# 1.net
KiCad netlist of a schematic drawn in Altium Designer
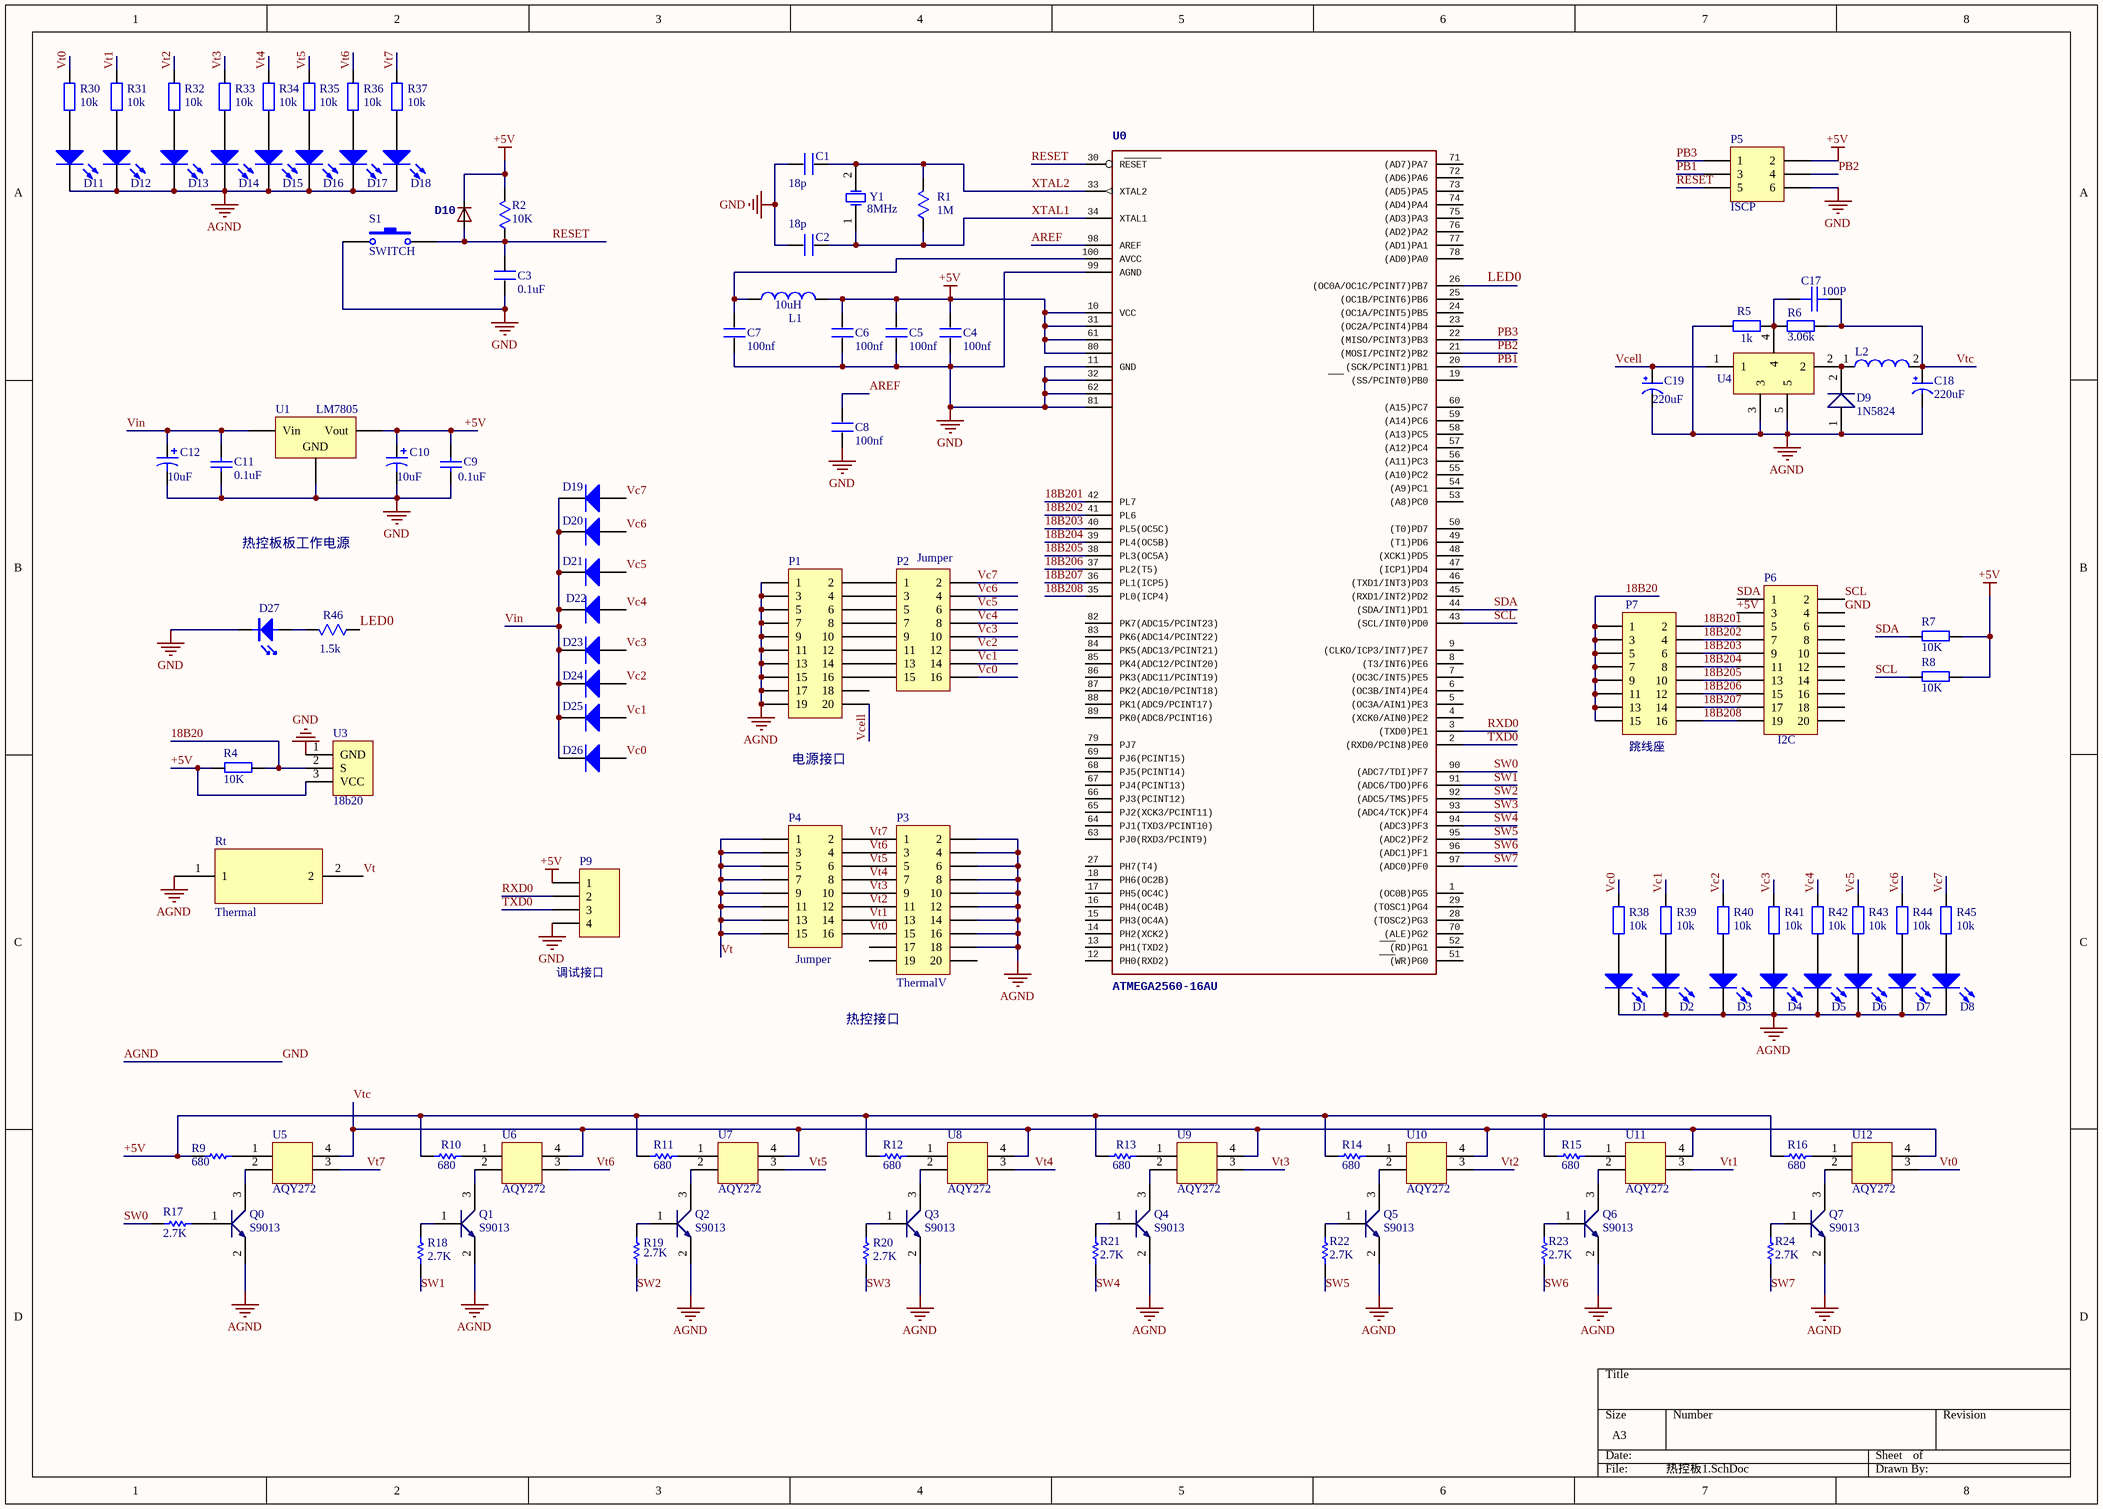
[diagram p0: 热控板1.SchDoc]

(export (version "E")
  (design (tool "Eeschema 10.0.6"))
  (components
    (comp (ref "C1") (value "18p") (footprint "CAPC3216M") (libsource (lib "STM32封装库") (part "C_1")))
    (comp (ref "C2") (value "18p") (footprint "CAPC3216M") (libsource (lib "STM32封装库") (part "C_1")))
    (comp (ref "C3") (value "0.1uF") (footprint "RESC3216M") (libsource (lib "STM32封装库") (part "C_3")))
    (comp (ref "C4") (value "100nf") (footprint "CAPC3216M") (libsource (lib "STM32封装库") (part "C")))
    (comp (ref "C5") (value "100nf") (footprint "CAPC3216M") (libsource (lib "STM32封装库") (part "C")))
    (comp (ref "C6") (value "100nf") (footprint "CAPC3216M") (libsource (lib "STM32封装库") (part "C")))
    (comp (ref "C7") (value "100nf") (footprint "CAPC3216M") (libsource (lib "STM32封装库") (part "C")))
    (comp (ref "C8") (value "100nf") (footprint "CAPC3216M") (libsource (lib "STM32封装库") (part "C")))
    (comp (ref "C9")
      (value "0.1uF")
      (footprint "CAPC3216M")
      (description "0.1uf")
      (fields (field (name "PUBLISHER") "Altium Limited"))
      (libsource (lib "Miscellaneous Devices") (part "Cap Semi"))
    )
    (comp (ref "C10")
      (value "10uF")
      (footprint "25V47uF")
      (description "10uf")
      (fields (field (name "PUBLISHER") "Altium Limited"))
      (libsource (lib "Miscellaneous Devices") (part "Cap Pol3"))
    )
    (comp (ref "C11")
      (value "0.1uF")
      (footprint "CAPC3216M")
      (description "0.1uf")
      (fields (field (name "PUBLISHER") "Altium Limited"))
      (libsource (lib "Miscellaneous Devices") (part "Cap"))
    )
    (comp (ref "C12")
      (value "10uF")
      (footprint "25V47uF")
      (description "10uf")
      (fields (field (name "PUBLISHER") "Altium Limited"))
      (libsource (lib "Miscellaneous Devices") (part "Cap Pol3"))
    )
    (comp (ref "C17")
      (value "100P")
      (footprint "CAPC3216M")
      (description "100p")
      (libsource (lib "YT1_SCH_99SE") (part "CAP"))
    )
    (comp (ref "C18") (value "220uF") (footprint "25V47uF") (libsource (lib "STM32封装库") (part "CAP")))
    (comp (ref "C19") (value "220uF") (footprint "25V47uF") (libsource (lib "STM32封装库") (part "CAP")))
    (comp (ref "D1")
      (value "LED")
      (footprint "LED")
      (description "Typical RED, GREEN, YELLOW, AMBER GaAs LED")
      (fields (field (name "PUBLISHER") "Altium Limited"))
      (libsource (lib "Miscellaneous Devices") (part "LED2"))
    )
    (comp (ref "D2")
      (value "LED")
      (footprint "LED")
      (description "Typical RED, GREEN, YELLOW, AMBER GaAs LED")
      (fields (field (name "PUBLISHER") "Altium Limited"))
      (libsource (lib "Miscellaneous Devices") (part "LED2"))
    )
    (comp (ref "D3")
      (value "LED")
      (footprint "LED")
      (description "Typical RED, GREEN, YELLOW, AMBER GaAs LED")
      (fields (field (name "PUBLISHER") "Altium Limited"))
      (libsource (lib "Miscellaneous Devices") (part "LED2"))
    )
    (comp (ref "D4")
      (value "LED")
      (footprint "LED")
      (description "Typical RED, GREEN, YELLOW, AMBER GaAs LED")
      (fields (field (name "PUBLISHER") "Altium Limited"))
      (libsource (lib "Miscellaneous Devices") (part "LED2"))
    )
    (comp (ref "D5")
      (value "LED")
      (footprint "LED")
      (description "Typical RED, GREEN, YELLOW, AMBER GaAs LED")
      (fields (field (name "PUBLISHER") "Altium Limited"))
      (libsource (lib "Miscellaneous Devices") (part "LED2"))
    )
    (comp (ref "D6")
      (value "LED")
      (footprint "LED")
      (description "Typical RED, GREEN, YELLOW, AMBER GaAs LED")
      (fields (field (name "PUBLISHER") "Altium Limited"))
      (libsource (lib "Miscellaneous Devices") (part "LED2"))
    )
    (comp (ref "D7")
      (value "LED")
      (footprint "LED")
      (description "Typical RED, GREEN, YELLOW, AMBER GaAs LED")
      (fields (field (name "PUBLISHER") "Altium Limited"))
      (libsource (lib "Miscellaneous Devices") (part "LED2"))
    )
    (comp (ref "D8")
      (value "LED")
      (footprint "LED")
      (description "Typical RED, GREEN, YELLOW, AMBER GaAs LED")
      (fields (field (name "PUBLISHER") "Altium Limited"))
      (libsource (lib "Miscellaneous Devices") (part "LED2"))
    )
    (comp (ref "D9") (value "1N5824") (footprint "DO214AC") (libsource (lib "STM32封装库") (part "1N5824")))
    (comp (ref "D10")
      (value "CD1206-S01575")
      (footprint "MINIMELF")
      (description "<b>DIODE</b>")
      (libsource (lib "Arduino_MEGA_2560-Rev3") (part "DIODE-MINIMELF"))
    )
    (comp (ref "D11")
      (value "LED")
      (footprint "LED")
      (description "Typical RED, GREEN, YELLOW, AMBER GaAs LED")
      (fields (field (name "PUBLISHER") "Altium Limited"))
      (libsource (lib "Miscellaneous Devices") (part "LED2"))
    )
    (comp (ref "D12")
      (value "LED")
      (footprint "LED")
      (description "Typical RED, GREEN, YELLOW, AMBER GaAs LED")
      (fields (field (name "PUBLISHER") "Altium Limited"))
      (libsource (lib "Miscellaneous Devices") (part "LED2"))
    )
    (comp (ref "D13")
      (value "LED")
      (footprint "LED")
      (description "Typical RED, GREEN, YELLOW, AMBER GaAs LED")
      (fields (field (name "PUBLISHER") "Altium Limited"))
      (libsource (lib "Miscellaneous Devices") (part "LED2"))
    )
    (comp (ref "D14")
      (value "LED")
      (footprint "LED")
      (description "Typical RED, GREEN, YELLOW, AMBER GaAs LED")
      (fields (field (name "PUBLISHER") "Altium Limited"))
      (libsource (lib "Miscellaneous Devices") (part "LED2"))
    )
    (comp (ref "D15")
      (value "LED")
      (footprint "LED")
      (description "Typical RED, GREEN, YELLOW, AMBER GaAs LED")
      (fields (field (name "PUBLISHER") "Altium Limited"))
      (libsource (lib "Miscellaneous Devices") (part "LED2"))
    )
    (comp (ref "D16")
      (value "LED")
      (footprint "LED")
      (description "Typical RED, GREEN, YELLOW, AMBER GaAs LED")
      (fields (field (name "PUBLISHER") "Altium Limited"))
      (libsource (lib "Miscellaneous Devices") (part "LED2"))
    )
    (comp (ref "D17")
      (value "LED")
      (footprint "LED")
      (description "Typical RED, GREEN, YELLOW, AMBER GaAs LED")
      (fields (field (name "PUBLISHER") "Altium Limited"))
      (libsource (lib "Miscellaneous Devices") (part "LED2"))
    )
    (comp (ref "D18")
      (value "LED")
      (footprint "LED")
      (description "Typical RED, GREEN, YELLOW, AMBER GaAs LED")
      (fields (field (name "PUBLISHER") "Altium Limited"))
      (libsource (lib "Miscellaneous Devices") (part "LED2"))
    )
    (comp (ref "D19")
      (value "1N4001")
      (footprint "SMB")
      (description "1 Amp General Purpose Rectifier")
      (fields (field (name "PUBLISHER") "Altium Limited"))
      (libsource (lib "Miscellaneous Devices") (part "Diode 1N4001"))
    )
    (comp (ref "D20")
      (value "1N4001")
      (footprint "SMB")
      (description "1 Amp General Purpose Rectifier")
      (fields (field (name "PUBLISHER") "Altium Limited"))
      (libsource (lib "Miscellaneous Devices") (part "Diode 1N4001"))
    )
    (comp (ref "D21")
      (value "1N4001")
      (footprint "SMB")
      (description "1 Amp General Purpose Rectifier")
      (fields (field (name "PUBLISHER") "Altium Limited"))
      (libsource (lib "Miscellaneous Devices") (part "Diode 1N4001"))
    )
    (comp (ref "D22")
      (value "1N4001")
      (footprint "SMB")
      (description "1 Amp General Purpose Rectifier")
      (fields (field (name "PUBLISHER") "Altium Limited"))
      (libsource (lib "Miscellaneous Devices") (part "Diode 1N4001"))
    )
    (comp (ref "D23")
      (value "1N4001")
      (footprint "SMB")
      (description "1 Amp General Purpose Rectifier")
      (fields (field (name "PUBLISHER") "Altium Limited"))
      (libsource (lib "Miscellaneous Devices") (part "Diode 1N4001"))
    )
    (comp (ref "D24")
      (value "1N4001")
      (footprint "SMB")
      (description "1 Amp General Purpose Rectifier")
      (fields (field (name "PUBLISHER") "Altium Limited"))
      (libsource (lib "Miscellaneous Devices") (part "Diode 1N4001"))
    )
    (comp (ref "D25")
      (value "1N4001")
      (footprint "SMB")
      (description "1 Amp General Purpose Rectifier")
      (fields (field (name "PUBLISHER") "Altium Limited"))
      (libsource (lib "Miscellaneous Devices") (part "Diode 1N4001"))
    )
    (comp (ref "D26")
      (value "1N4001")
      (footprint "SMB")
      (description "1 Amp General Purpose Rectifier")
      (fields (field (name "PUBLISHER") "Altium Limited"))
      (libsource (lib "Miscellaneous Devices") (part "Diode 1N4001"))
    )
    (comp (ref "D27") (value "DS0") (footprint "常用元件封装:LED") (libsource (lib "YT1_SCH_99SE") (part "LED")))
    (comp (ref "L1")
      (value "10uH")
      (footprint "INDC3216M")
      (description "Inductor")
      (fields (field (name "PUBLISHER") "Altium Limited"))
      (libsource (lib "Miscellaneous Devices") (part "Inductor"))
    )
    (comp (ref "L2")
      (value "inductance")
      (footprint "INDUCTANCE_1")
      (libsource (lib "STM32封装库") (part "inductance"))
    )
    (comp (ref "P1")
      (value "Power Interface")
      (footprint "HDR2X10")
      (description "Header, 10-Pin, Dual row")
      (fields (field (name "PUBLISHER") "Altium Limited"))
      (libsource (lib "Miscellaneous Connectors") (part "Header 10X2"))
    )
    (comp (ref "P2")
      (value "Jumper")
      (footprint "HDR2X8")
      (description "Header, 8-Pin, Dual row")
      (fields (field (name "PUBLISHER") "Altium Limited"))
      (libsource (lib "Miscellaneous Connectors") (part "Header 8X2"))
    )
    (comp (ref "P3")
      (value "ThermalV")
      (footprint "HDR2X10")
      (description "Header, 10-Pin, Dual row")
      (fields (field (name "PUBLISHER") "Altium Limited"))
      (libsource (lib "Miscellaneous Connectors") (part "Header 10X2"))
    )
    (comp (ref "P4")
      (value "Jumper")
      (footprint "tiepianpeizhen")
      (description "Header, 8-Pin, Dual row")
      (fields (field (name "PUBLISHER") "Altium Limited"))
      (libsource (lib "Miscellaneous Connectors") (part "Header 8X2"))
    )
    (comp (ref "P5")
      (value "ISCP")
      (footprint "HDR2X3")
      (description "Header, 3-Pin, Dual row")
      (fields (field (name "PUBLISHER") "Altium Limited"))
      (libsource (lib "Miscellaneous Connectors") (part "Header 3X2"))
    )
    (comp (ref "P6")
      (value "I2C")
      (footprint "HDR2X10")
      (description "Header, 10-Pin, Dual row")
      (fields (field (name "PUBLISHER") "Altium Limited"))
      (libsource (lib "Miscellaneous Connectors") (part "Header 10X2"))
    )
    (comp (ref "P7")
      (value "跳线座")
      (footprint "HDR2X8")
      (description "Header, 8-Pin, Dual row")
      (fields (field (name "PUBLISHER") "Altium Limited"))
      (libsource (lib "Miscellaneous Connectors") (part "Header 8X2"))
    )
    (comp (ref "P9")
      (value "调试接口")
      (footprint "HDR1X4")
      (description "Header, 4-Pin")
      (fields (field (name "PUBLISHER") "Altium Limited"))
      (libsource (lib "Miscellaneous Connectors") (part "Header 4"))
    )
    (comp (ref "Q0") (value "S9013") (footprint "SOT23") (libsource (lib "常用元件库") (part "S9013")))
    (comp (ref "Q1") (value "S9013") (footprint "SOT23") (libsource (lib "常用元件库") (part "S9013")))
    (comp (ref "Q2") (value "S9013") (footprint "SOT23") (libsource (lib "常用元件库") (part "S9013")))
    (comp (ref "Q3") (value "S9013") (footprint "SOT23") (libsource (lib "常用元件库") (part "S9013")))
    (comp (ref "Q4") (value "S9013") (footprint "SOT23") (libsource (lib "常用元件库") (part "S9013")))
    (comp (ref "Q5") (value "S9013") (footprint "SOT23") (libsource (lib "常用元件库") (part "S9013")))
    (comp (ref "Q6") (value "S9013") (footprint "SOT23") (libsource (lib "常用元件库") (part "S9013")))
    (comp (ref "Q7") (value "S9013") (footprint "SOT23") (libsource (lib "常用元件库") (part "S9013")))
    (comp (ref "R1") (value "1M") (footprint "RESC3216M") (libsource (lib "YT1_SCH_99SE") (part "RES")))
    (comp (ref "R2") (value "10K") (footprint "RESC3216M") (libsource (lib "YT1_SCH_99SE") (part "RES")))
    (comp (ref "R4") (value "10K") (footprint "RESC3216M") (libsource (lib "STM32封装库") (part "R")))
    (comp (ref "R5")
      (value "1k")
      (footprint "RESC3216M")
      (description "Resistor")
      (fields (field (name "PUBLISHER") "Altium Limited"))
      (libsource (lib "") (part "Res2_1"))
    )
    (comp (ref "R6")
      (value "3.06k")
      (footprint "RESC3216M")
      (description "Resistor")
      (fields (field (name "Comment") "5.1k") (field (name "PUBLISHER") "Altium Limited"))
      (libsource (lib "") (part "Res2_1"))
    )
    (comp (ref "R7") (value "10K") (footprint "RESC3216M") (libsource (lib "STM32封装库") (part "R")))
    (comp (ref "R8") (value "10K") (footprint "RESC3216M") (libsource (lib "STM32封装库") (part "R")))
    (comp (ref "R9")
      (value "680")
      (footprint "RESC3216M")
      (description "resistance")
      (libsource (lib "Sat_Integrated_Library") (part "Res"))
    )
    (comp (ref "R10")
      (value "680")
      (footprint "RESC3216M")
      (description "resistance")
      (libsource (lib "Sat_Integrated_Library") (part "Res"))
    )
    (comp (ref "R11")
      (value "680")
      (footprint "RESC3216M")
      (description "resistance")
      (libsource (lib "Sat_Integrated_Library") (part "Res"))
    )
    (comp (ref "R12")
      (value "680")
      (footprint "RESC3216M")
      (description "resistance")
      (libsource (lib "Sat_Integrated_Library") (part "Res"))
    )
    (comp (ref "R13")
      (value "680")
      (footprint "RESC3216M")
      (description "resistance")
      (libsource (lib "Sat_Integrated_Library") (part "Res"))
    )
    (comp (ref "R14")
      (value "680")
      (footprint "RESC3216M")
      (description "resistance")
      (libsource (lib "Sat_Integrated_Library") (part "Res"))
    )
    (comp (ref "R15")
      (value "680")
      (footprint "RESC3216M")
      (description "resistance")
      (libsource (lib "Sat_Integrated_Library") (part "Res"))
    )
    (comp (ref "R16")
      (value "680")
      (footprint "RESC3216M")
      (description "resistance")
      (libsource (lib "Sat_Integrated_Library") (part "Res"))
    )
    (comp (ref "R17")
      (value "2.7K")
      (footprint "RESC3216M")
      (description "resistance")
      (libsource (lib "Sat_Integrated_Library") (part "Res"))
    )
    (comp (ref "R18")
      (value "2.7K")
      (footprint "RESC3216M")
      (description "resistance")
      (libsource (lib "Sat_Integrated_Library") (part "Res"))
    )
    (comp (ref "R19")
      (value "2.7K")
      (footprint "RESC3216M")
      (description "resistance")
      (libsource (lib "Sat_Integrated_Library") (part "Res"))
    )
    (comp (ref "R20")
      (value "2.7K")
      (footprint "RESC3216M")
      (description "resistance")
      (libsource (lib "Sat_Integrated_Library") (part "Res"))
    )
    (comp (ref "R21")
      (value "2.7K")
      (footprint "RESC3216M")
      (description "resistance")
      (libsource (lib "Sat_Integrated_Library") (part "Res"))
    )
    (comp (ref "R22")
      (value "2.7K")
      (footprint "RESC3216M")
      (description "resistance")
      (libsource (lib "Sat_Integrated_Library") (part "Res"))
    )
    (comp (ref "R23")
      (value "2.7K")
      (footprint "RESC3216M")
      (description "resistance")
      (libsource (lib "Sat_Integrated_Library") (part "Res"))
    )
    (comp (ref "R24")
      (value "2.7K")
      (footprint "RESC3216M")
      (description "resistance")
      (libsource (lib "Sat_Integrated_Library") (part "Res"))
    )
    (comp (ref "R30")
      (value "10k")
      (footprint "RESC3216M")
      (description "5.1k")
      (fields (field (name "Comment") "10K") (field (name "PUBLISHER") "Altium Limited"))
      (libsource (lib "Miscellaneous Devices") (part "Res2"))
    )
    (comp (ref "R31")
      (value "10k")
      (footprint "RESC3216M")
      (description "5.1k")
      (fields (field (name "Comment") "10K") (field (name "PUBLISHER") "Altium Limited"))
      (libsource (lib "Miscellaneous Devices") (part "Res2"))
    )
    (comp (ref "R32")
      (value "10k")
      (footprint "RESC3216M")
      (description "5.1k")
      (fields (field (name "Comment") "10K") (field (name "PUBLISHER") "Altium Limited"))
      (libsource (lib "Miscellaneous Devices") (part "Res2"))
    )
    (comp (ref "R33")
      (value "10k")
      (footprint "RESC3216M")
      (description "5.1k")
      (fields (field (name "Comment") "10K") (field (name "PUBLISHER") "Altium Limited"))
      (libsource (lib "Miscellaneous Devices") (part "Res2"))
    )
    (comp (ref "R34")
      (value "10k")
      (footprint "RESC3216M")
      (description "5.1k")
      (fields (field (name "Comment") "10K") (field (name "PUBLISHER") "Altium Limited"))
      (libsource (lib "Miscellaneous Devices") (part "Res2"))
    )
    (comp (ref "R35")
      (value "10k")
      (footprint "RESC3216M")
      (description "5.1k")
      (fields (field (name "Comment") "10K") (field (name "PUBLISHER") "Altium Limited"))
      (libsource (lib "Miscellaneous Devices") (part "Res2"))
    )
    (comp (ref "R36")
      (value "10k")
      (footprint "RESC3216M")
      (description "5.1k")
      (fields (field (name "Comment") "10K") (field (name "PUBLISHER") "Altium Limited"))
      (libsource (lib "Miscellaneous Devices") (part "Res2"))
    )
    (comp (ref "R37")
      (value "10k")
      (footprint "RESC3216M")
      (description "5.1k")
      (fields (field (name "Comment") "10K") (field (name "PUBLISHER") "Altium Limited"))
      (libsource (lib "Miscellaneous Devices") (part "Res2"))
    )
    (comp (ref "R38")
      (value "10k")
      (footprint "RESC3216M")
      (description "5.1k")
      (fields (field (name "Comment") "10K") (field (name "PUBLISHER") "Altium Limited"))
      (libsource (lib "Miscellaneous Devices") (part "Res2"))
    )
    (comp (ref "R39")
      (value "10k")
      (footprint "RESC3216M")
      (description "5.1k")
      (fields (field (name "Comment") "10K") (field (name "PUBLISHER") "Altium Limited"))
      (libsource (lib "Miscellaneous Devices") (part "Res2"))
    )
    (comp (ref "R40")
      (value "10k")
      (footprint "RESC3216M")
      (description "5.1k")
      (fields (field (name "Comment") "10K") (field (name "PUBLISHER") "Altium Limited"))
      (libsource (lib "Miscellaneous Devices") (part "Res2"))
    )
    (comp (ref "R41")
      (value "10k")
      (footprint "RESC3216M")
      (description "5.1k")
      (fields (field (name "Comment") "10K") (field (name "PUBLISHER") "Altium Limited"))
      (libsource (lib "Miscellaneous Devices") (part "Res2"))
    )
    (comp (ref "R42")
      (value "10k")
      (footprint "RESC3216M")
      (description "5.1k")
      (fields (field (name "Comment") "10K") (field (name "PUBLISHER") "Altium Limited"))
      (libsource (lib "Miscellaneous Devices") (part "Res2"))
    )
    (comp (ref "R43")
      (value "10k")
      (footprint "RESC3216M")
      (description "5.1k")
      (fields (field (name "Comment") "10K") (field (name "PUBLISHER") "Altium Limited"))
      (libsource (lib "Miscellaneous Devices") (part "Res2"))
    )
    (comp (ref "R44")
      (value "10k")
      (footprint "RESC3216M")
      (description "5.1k")
      (fields (field (name "Comment") "10K") (field (name "PUBLISHER") "Altium Limited"))
      (libsource (lib "Miscellaneous Devices") (part "Res2"))
    )
    (comp (ref "R45")
      (value "10k")
      (footprint "RESC3216M")
      (description "5.1k")
      (fields (field (name "Comment") "10K") (field (name "PUBLISHER") "Altium Limited"))
      (libsource (lib "Miscellaneous Devices") (part "Res2"))
    )
    (comp (ref "R46") (value "1.5k") (footprint "RESC3216m") (libsource (lib "YT1_SCH_99SE") (part "RES")))
    (comp (ref "Rt") (value "Thermal") (footprint "Thermal Res") (libsource (lib "jrdz") (part "jrdz")))
    (comp (ref "S1")
      (value "SWITCH")
      (footprint "PUSH BUTTON 6x6")
      (libsource (lib "STM32封装库") (part "SWITCH"))
    )
    (comp (ref "U0")
      (value "ATMEGA2560-16AU")
      (footprint "TQFP100")
      (libsource (lib "Arduino_MEGA_2560-Rev3") (part "ATMEGA2560AU"))
    )
    (comp (ref "U1")
      (value "LM7805")
      (footprint "DPAK-3")
      (description "Voltage Regulator")
      (fields (field (name "PUBLISHER") "Altium Limited"))
      (libsource (lib "Miscellaneous Devices") (part "Volt Reg"))
    )
    (comp (ref "U3") (value "18b20") (footprint "常用元件封装:TO92") (libsource (lib "常用元件库") (part "18b20")))
    (comp (ref "U4")
      (value "LM2596SADJ")
      (footprint "TO263_5")
      (libsource (lib "STM32封装库") (part "LM2596SADJ"))
    )
    (comp (ref "U5")
      (value "AQY272")
      (footprint "AQY272")
      (libsource (lib "Sat_Integrated_Library") (part "AQY272"))
    )
    (comp (ref "U6")
      (value "AQY272")
      (footprint "AQY272")
      (libsource (lib "Sat_Integrated_Library") (part "AQY272"))
    )
    (comp (ref "U7")
      (value "AQY272")
      (footprint "AQY272")
      (libsource (lib "Sat_Integrated_Library") (part "AQY272"))
    )
    (comp (ref "U8")
      (value "AQY272")
      (footprint "AQY272")
      (libsource (lib "Sat_Integrated_Library") (part "AQY272"))
    )
    (comp (ref "U9")
      (value "AQY272")
      (footprint "AQY272")
      (libsource (lib "Sat_Integrated_Library") (part "AQY272"))
    )
    (comp (ref "U10")
      (value "AQY272")
      (footprint "AQY272")
      (libsource (lib "Sat_Integrated_Library") (part "AQY272"))
    )
    (comp (ref "U11")
      (value "AQY272")
      (footprint "AQY272")
      (libsource (lib "Sat_Integrated_Library") (part "AQY272"))
    )
    (comp (ref "U12")
      (value "AQY272")
      (footprint "AQY272")
      (libsource (lib "Sat_Integrated_Library") (part "AQY272"))
    )
    (comp (ref "Y1")
      (value "8MHz")
      (footprint "XTAL_US")
      (description "Crystal Oscillator")
      (fields (field (name "PUBLISHER") "Altium Limited"))
      (libsource (lib "STM32封装库") (part "XTAL"))
    )
  )
  (nets
    (net (code "1") (name "+5V") (class "Default")
      (node (ref "C10") (pin "1") (pinfunction "1_1") (pintype "passive"))
      (node (ref "C4") (pin "2") (pintype "passive"))
      (node (ref "C5") (pin "2") (pintype "passive"))
      (node (ref "C6") (pin "2") (pintype "passive"))
      (node (ref "C9") (pin "2") (pinfunction "2_2") (pintype "passive"))
      (node (ref "D10") (pin "C") (pinfunction "C_C") (pintype "passive"))
      (node (ref "L1") (pin "2") (pinfunction "2_2") (pintype "passive"))
      (node (ref "P5") (pin "2") (pinfunction "2_2") (pintype "passive"))
      (node (ref "P6") (pin "3") (pinfunction "3_3") (pintype "passive"))
      (node (ref "P9") (pin "1") (pinfunction "1_1") (pintype "passive"))
      (node (ref "R10") (pin "1") (pinfunction "1_1") (pintype "passive"))
      (node (ref "R11") (pin "1") (pinfunction "1_1") (pintype "passive"))
      (node (ref "R12") (pin "1") (pinfunction "1_1") (pintype "passive"))
      (node (ref "R13") (pin "1") (pinfunction "1_1") (pintype "passive"))
      (node (ref "R14") (pin "1") (pinfunction "1_1") (pintype "passive"))
      (node (ref "R15") (pin "1") (pinfunction "1_1") (pintype "passive"))
      (node (ref "R16") (pin "1") (pinfunction "1_1") (pintype "passive"))
      (node (ref "R2") (pin "2") (pinfunction "2_2") (pintype "passive"))
      (node (ref "R4") (pin "2") (pintype "passive"))
      (node (ref "R7") (pin "1") (pintype "passive"))
      (node (ref "R8") (pin "1") (pintype "passive"))
      (node (ref "R9") (pin "1") (pinfunction "1_1") (pintype "passive"))
      (node (ref "U0") (pin "10") (pinfunction "VCC_10") (pintype "power_in"))
      (node (ref "U0") (pin "31") (pinfunction "VCC1_31") (pintype "power_in"))
      (node (ref "U0") (pin "61") (pinfunction "VCC2_61") (pintype "power_in"))
      (node (ref "U0") (pin "80") (pinfunction "VCC3_80") (pintype "power_in"))
      (node (ref "U1") (pin "3") (pinfunction "Vout_3") (pintype "passive"))
      (node (ref "U3") (pin "3") (pinfunction "VCC_3") (pintype "passive"))
    )
    (net (code "2") (name "/18B20") (class "Default")
      (node (ref "P7") (pin "1") (pinfunction "1_1") (pintype "passive"))
      (node (ref "P7") (pin "11") (pinfunction "11_11") (pintype "passive"))
      (node (ref "P7") (pin "13") (pinfunction "13_13") (pintype "passive"))
      (node (ref "P7") (pin "15") (pinfunction "15_15") (pintype "passive"))
      (node (ref "P7") (pin "3") (pinfunction "3_3") (pintype "passive"))
      (node (ref "P7") (pin "5") (pinfunction "5_5") (pintype "passive"))
      (node (ref "P7") (pin "7") (pinfunction "7_7") (pintype "passive"))
      (node (ref "P7") (pin "9") (pinfunction "9_9") (pintype "passive"))
      (node (ref "R4") (pin "1") (pintype "passive"))
      (node (ref "U3") (pin "2") (pinfunction "S_2") (pintype "passive"))
    )
    (net (code "3") (name "/18B201") (class "Default")
      (node (ref "P6") (pin "5") (pinfunction "5_5") (pintype "passive"))
      (node (ref "P7") (pin "2") (pinfunction "2_2") (pintype "passive"))
      (node (ref "U0") (pin "42") (pinfunction "PL7_42") (pintype "passive"))
    )
    (net (code "4") (name "/18B202") (class "Default")
      (node (ref "P6") (pin "7") (pinfunction "7_7") (pintype "passive"))
      (node (ref "P7") (pin "4") (pinfunction "4_4") (pintype "passive"))
      (node (ref "U0") (pin "41") (pinfunction "PL6_41") (pintype "passive"))
    )
    (net (code "5") (name "/18B203") (class "Default")
      (node (ref "P6") (pin "9") (pinfunction "9_9") (pintype "passive"))
      (node (ref "P7") (pin "6") (pinfunction "6_6") (pintype "passive"))
      (node (ref "U0") (pin "40") (pinfunction "PL5(OC5C)_40") (pintype "passive"))
    )
    (net (code "6") (name "/18B204") (class "Default")
      (node (ref "P6") (pin "11") (pinfunction "11_11") (pintype "passive"))
      (node (ref "P7") (pin "8") (pinfunction "8_8") (pintype "passive"))
      (node (ref "U0") (pin "39") (pinfunction "PL4(OC5B)_39") (pintype "passive"))
    )
    (net (code "7") (name "/18B205") (class "Default")
      (node (ref "P6") (pin "13") (pinfunction "13_13") (pintype "passive"))
      (node (ref "P7") (pin "10") (pinfunction "10_10") (pintype "passive"))
      (node (ref "U0") (pin "38") (pinfunction "PL3(OC5A)_38") (pintype "passive"))
    )
    (net (code "8") (name "/18B206") (class "Default")
      (node (ref "P6") (pin "15") (pinfunction "15_15") (pintype "passive"))
      (node (ref "P7") (pin "12") (pinfunction "12_12") (pintype "passive"))
      (node (ref "U0") (pin "37") (pinfunction "PL2(T5)_37") (pintype "passive"))
    )
    (net (code "9") (name "/18B207") (class "Default")
      (node (ref "P6") (pin "17") (pinfunction "17_17") (pintype "passive"))
      (node (ref "P7") (pin "14") (pinfunction "14_14") (pintype "passive"))
      (node (ref "U0") (pin "36") (pinfunction "PL1(ICP5)_36") (pintype "passive"))
    )
    (net (code "10") (name "/18B208") (class "Default")
      (node (ref "P6") (pin "19") (pinfunction "19_19") (pintype "passive"))
      (node (ref "P7") (pin "16") (pinfunction "16_16") (pintype "passive"))
      (node (ref "U0") (pin "35") (pinfunction "PL0(ICP4)_35") (pintype "passive"))
    )
    (net (code "11") (name "/AREF") (class "Default")
      (node (ref "C8") (pin "2") (pintype "passive"))
      (node (ref "U0") (pin "98") (pinfunction "AREF_98") (pintype "passive"))
    )
    (net (code "12") (name "/LED0") (class "Default")
      (node (ref "R46") (pin "1") (pinfunction "1_1") (pintype "passive"))
      (node (ref "U0") (pin "26") (pinfunction "(OC0A/OC1C/PCINT7)PB7_26") (pintype "passive"))
    )
    (net (code "13") (name "/PB1") (class "Default")
      (node (ref "P5") (pin "3") (pinfunction "3_3") (pintype "passive"))
      (node (ref "U0") (pin "20") (pinfunction "(SCK/PCINT1)PB1_20") (pintype "passive"))
    )
    (net (code "14") (name "/PB2") (class "Default")
      (node (ref "P5") (pin "4") (pinfunction "4_4") (pintype "passive"))
      (node (ref "U0") (pin "21") (pinfunction "(MOSI/PCINT2)PB2_21") (pintype "passive"))
    )
    (net (code "15") (name "/PB3") (class "Default")
      (node (ref "P5") (pin "1") (pinfunction "1_1") (pintype "passive"))
      (node (ref "U0") (pin "22") (pinfunction "(MISO/PCINT3)PB3_22") (pintype "passive"))
    )
    (net (code "16") (name "/RESET") (class "Default")
      (node (ref "C3") (pin "2") (pintype "passive"))
      (node (ref "D10") (pin "A") (pinfunction "A_A") (pintype "passive"))
      (node (ref "P5") (pin "5") (pinfunction "5_5") (pintype "passive"))
      (node (ref "R2") (pin "1") (pinfunction "1_1") (pintype "passive"))
      (node (ref "S1") (pin "2") (pinfunction "2_2") (pintype "passive"))
      (node (ref "U0") (pin "30") (pinfunction "RESET_30") (pintype "passive"))
    )
    (net (code "17") (name "/RXD0") (class "Default")
      (node (ref "P9") (pin "2") (pinfunction "2_2") (pintype "passive"))
      (node (ref "U0") (pin "3") (pinfunction "(TXD0)PE1_3") (pintype "passive"))
    )
    (net (code "18") (name "/SCL") (class "Default")
      (node (ref "P6") (pin "2") (pinfunction "2_2") (pintype "passive"))
      (node (ref "R8") (pin "2") (pintype "passive"))
      (node (ref "U0") (pin "43") (pinfunction "(SCL/INT0)PD0_43") (pintype "passive"))
    )
    (net (code "19") (name "/SDA") (class "Default")
      (node (ref "P6") (pin "1") (pinfunction "1_1") (pintype "passive"))
      (node (ref "R7") (pin "2") (pintype "passive"))
      (node (ref "U0") (pin "44") (pinfunction "(SDA/INT1)PD1_44") (pintype "passive"))
    )
    (net (code "20") (name "/SW0") (class "Default")
      (node (ref "R17") (pin "1") (pinfunction "1_1") (pintype "passive"))
      (node (ref "U0") (pin "90") (pinfunction "(ADC7/TDI)PF7_90") (pintype "passive"))
    )
    (net (code "21") (name "/SW1") (class "Default")
      (node (ref "R18") (pin "1") (pinfunction "1_1") (pintype "passive"))
      (node (ref "U0") (pin "91") (pinfunction "(ADC6/TDO)PF6_91") (pintype "passive"))
    )
    (net (code "22") (name "/SW2") (class "Default")
      (node (ref "R19") (pin "1") (pinfunction "1_1") (pintype "passive"))
      (node (ref "U0") (pin "92") (pinfunction "(ADC5/TMS)PF5_92") (pintype "passive"))
    )
    (net (code "23") (name "/SW3") (class "Default")
      (node (ref "R20") (pin "1") (pinfunction "1_1") (pintype "passive"))
      (node (ref "U0") (pin "93") (pinfunction "(ADC4/TCK)PF4_93") (pintype "passive"))
    )
    (net (code "24") (name "/SW4") (class "Default")
      (node (ref "R21") (pin "1") (pinfunction "1_1") (pintype "passive"))
      (node (ref "U0") (pin "94") (pinfunction "(ADC3)PF3_94") (pintype "passive"))
    )
    (net (code "25") (name "/SW5") (class "Default")
      (node (ref "R22") (pin "1") (pinfunction "1_1") (pintype "passive"))
      (node (ref "U0") (pin "95") (pinfunction "(ADC2)PF2_95") (pintype "passive"))
    )
    (net (code "26") (name "/SW6") (class "Default")
      (node (ref "R23") (pin "1") (pinfunction "1_1") (pintype "passive"))
      (node (ref "U0") (pin "96") (pinfunction "(ADC1)PF1_96") (pintype "passive"))
    )
    (net (code "27") (name "/SW7") (class "Default")
      (node (ref "R24") (pin "1") (pinfunction "1_1") (pintype "passive"))
      (node (ref "U0") (pin "97") (pinfunction "(ADC0)PF0_97") (pintype "passive"))
    )
    (net (code "28") (name "/TXD0") (class "Default")
      (node (ref "P9") (pin "3") (pinfunction "3_3") (pintype "passive"))
      (node (ref "U0") (pin "2") (pinfunction "(RXD0/PCIN8)PE0_2") (pintype "passive"))
    )
    (net (code "29") (name "/Vc0") (class "Default")
      (node (ref "D26") (pin "1") (pinfunction "A_1") (pintype "passive"))
      (node (ref "P2") (pin "16") (pinfunction "16_16") (pintype "passive"))
      (node (ref "R38") (pin "2") (pinfunction "2_2") (pintype "passive"))
    )
    (net (code "30") (name "/Vc1") (class "Default")
      (node (ref "D25") (pin "1") (pinfunction "A_1") (pintype "passive"))
      (node (ref "P2") (pin "14") (pinfunction "14_14") (pintype "passive"))
      (node (ref "R39") (pin "2") (pinfunction "2_2") (pintype "passive"))
    )
    (net (code "31") (name "/Vc2") (class "Default")
      (node (ref "D24") (pin "1") (pinfunction "A_1") (pintype "passive"))
      (node (ref "P2") (pin "12") (pinfunction "12_12") (pintype "passive"))
      (node (ref "R40") (pin "2") (pinfunction "2_2") (pintype "passive"))
    )
    (net (code "32") (name "/Vc3") (class "Default")
      (node (ref "D23") (pin "1") (pinfunction "A_1") (pintype "passive"))
      (node (ref "P2") (pin "10") (pinfunction "10_10") (pintype "passive"))
      (node (ref "R41") (pin "2") (pinfunction "2_2") (pintype "passive"))
    )
    (net (code "33") (name "/Vc4") (class "Default")
      (node (ref "D22") (pin "1") (pinfunction "A_1") (pintype "passive"))
      (node (ref "P2") (pin "8") (pinfunction "8_8") (pintype "passive"))
      (node (ref "R42") (pin "2") (pinfunction "2_2") (pintype "passive"))
    )
    (net (code "34") (name "/Vc5") (class "Default")
      (node (ref "D21") (pin "1") (pinfunction "A_1") (pintype "passive"))
      (node (ref "P2") (pin "6") (pinfunction "6_6") (pintype "passive"))
      (node (ref "R43") (pin "2") (pinfunction "2_2") (pintype "passive"))
    )
    (net (code "35") (name "/Vc6") (class "Default")
      (node (ref "D20") (pin "1") (pinfunction "A_1") (pintype "passive"))
      (node (ref "P2") (pin "4") (pinfunction "4_4") (pintype "passive"))
      (node (ref "R44") (pin "2") (pinfunction "2_2") (pintype "passive"))
    )
    (net (code "36") (name "/Vc7") (class "Default")
      (node (ref "D19") (pin "1") (pinfunction "A_1") (pintype "passive"))
      (node (ref "P2") (pin "2") (pinfunction "2_2") (pintype "passive"))
      (node (ref "R45") (pin "2") (pinfunction "2_2") (pintype "passive"))
    )
    (net (code "37") (name "/Vcell") (class "Default")
      (node (ref "C19") (pin "1") (pinfunction "VCC_1") (pintype "passive"))
      (node (ref "P1") (pin "20") (pinfunction "20_20") (pintype "passive"))
      (node (ref "U4") (pin "1") (pinfunction "1_1") (pintype "passive"))
    )
    (net (code "38") (name "/Vin") (class "Default")
      (node (ref "C11") (pin "2") (pinfunction "2_2") (pintype "passive"))
      (node (ref "C12") (pin "1") (pinfunction "1_1") (pintype "passive"))
      (node (ref "D19") (pin "2") (pinfunction "K_2") (pintype "passive"))
      (node (ref "D20") (pin "2") (pinfunction "K_2") (pintype "passive"))
      (node (ref "D21") (pin "2") (pinfunction "K_2") (pintype "passive"))
      (node (ref "D22") (pin "2") (pinfunction "K_2") (pintype "passive"))
      (node (ref "D23") (pin "2") (pinfunction "K_2") (pintype "passive"))
      (node (ref "D24") (pin "2") (pinfunction "K_2") (pintype "passive"))
      (node (ref "D25") (pin "2") (pinfunction "K_2") (pintype "passive"))
      (node (ref "D26") (pin "2") (pinfunction "K_2") (pintype "passive"))
      (node (ref "U1") (pin "1") (pinfunction "Vin_1") (pintype "passive"))
    )
    (net (code "39") (name "/Vt") (class "Default")
      (node (ref "P4") (pin "1") (pinfunction "1_1") (pintype "passive"))
      (node (ref "P4") (pin "11") (pinfunction "11_11") (pintype "passive"))
      (node (ref "P4") (pin "13") (pinfunction "13_13") (pintype "passive"))
      (node (ref "P4") (pin "15") (pinfunction "15_15") (pintype "passive"))
      (node (ref "P4") (pin "3") (pinfunction "3_3") (pintype "passive"))
      (node (ref "P4") (pin "5") (pinfunction "5_5") (pintype "passive"))
      (node (ref "P4") (pin "7") (pinfunction "7_7") (pintype "passive"))
      (node (ref "P4") (pin "9") (pinfunction "9_9") (pintype "passive"))
      (node (ref "Rt") (pin "2") (pinfunction "2_2") (pintype "passive"))
    )
    (net (code "40") (name "/Vt0") (class "Default")
      (node (ref "P3") (pin "15") (pinfunction "15_15") (pintype "passive"))
      (node (ref "P4") (pin "16") (pinfunction "16_16") (pintype "passive"))
      (node (ref "R30") (pin "2") (pinfunction "2_2") (pintype "passive"))
      (node (ref "U12") (pin "3") (pinfunction "3_3") (pintype "passive"))
    )
    (net (code "41") (name "/Vt1") (class "Default")
      (node (ref "P3") (pin "13") (pinfunction "13_13") (pintype "passive"))
      (node (ref "P4") (pin "14") (pinfunction "14_14") (pintype "passive"))
      (node (ref "R31") (pin "2") (pinfunction "2_2") (pintype "passive"))
      (node (ref "U11") (pin "3") (pinfunction "3_3") (pintype "passive"))
    )
    (net (code "42") (name "/Vt2") (class "Default")
      (node (ref "P3") (pin "11") (pinfunction "11_11") (pintype "passive"))
      (node (ref "P4") (pin "12") (pinfunction "12_12") (pintype "passive"))
      (node (ref "R32") (pin "2") (pinfunction "2_2") (pintype "passive"))
      (node (ref "U10") (pin "3") (pinfunction "3_3") (pintype "passive"))
    )
    (net (code "43") (name "/Vt3") (class "Default")
      (node (ref "P3") (pin "9") (pinfunction "9_9") (pintype "passive"))
      (node (ref "P4") (pin "10") (pinfunction "10_10") (pintype "passive"))
      (node (ref "R33") (pin "2") (pinfunction "2_2") (pintype "passive"))
      (node (ref "U9") (pin "3") (pinfunction "3_3") (pintype "passive"))
    )
    (net (code "44") (name "/Vt4") (class "Default")
      (node (ref "P3") (pin "7") (pinfunction "7_7") (pintype "passive"))
      (node (ref "P4") (pin "8") (pinfunction "8_8") (pintype "passive"))
      (node (ref "R34") (pin "2") (pinfunction "2_2") (pintype "passive"))
      (node (ref "U8") (pin "3") (pinfunction "3_3") (pintype "passive"))
    )
    (net (code "45") (name "/Vt5") (class "Default")
      (node (ref "P3") (pin "5") (pinfunction "5_5") (pintype "passive"))
      (node (ref "P4") (pin "6") (pinfunction "6_6") (pintype "passive"))
      (node (ref "R35") (pin "2") (pinfunction "2_2") (pintype "passive"))
      (node (ref "U7") (pin "3") (pinfunction "3_3") (pintype "passive"))
    )
    (net (code "46") (name "/Vt6") (class "Default")
      (node (ref "P3") (pin "3") (pinfunction "3_3") (pintype "passive"))
      (node (ref "P4") (pin "4") (pinfunction "4_4") (pintype "passive"))
      (node (ref "R36") (pin "2") (pinfunction "2_2") (pintype "passive"))
      (node (ref "U6") (pin "3") (pinfunction "3_3") (pintype "passive"))
    )
    (net (code "47") (name "/Vt7") (class "Default")
      (node (ref "P3") (pin "1") (pinfunction "1_1") (pintype "passive"))
      (node (ref "P4") (pin "2") (pinfunction "2_2") (pintype "passive"))
      (node (ref "R37") (pin "2") (pinfunction "2_2") (pintype "passive"))
      (node (ref "U5") (pin "3") (pinfunction "3_3") (pintype "passive"))
    )
    (net (code "48") (name "/Vtc") (class "Default")
      (node (ref "C17") (pin "2") (pinfunction "2_2") (pintype "passive"))
      (node (ref "C18") (pin "1") (pinfunction "VCC_1") (pintype "passive"))
      (node (ref "L2") (pin "2") (pinfunction "2_2") (pintype "passive"))
      (node (ref "R6") (pin "1") (pinfunction "1_1") (pintype "passive"))
      (node (ref "U10") (pin "4") (pinfunction "4_4") (pintype "passive"))
      (node (ref "U11") (pin "4") (pinfunction "4_4") (pintype "passive"))
      (node (ref "U12") (pin "4") (pinfunction "4_4") (pintype "passive"))
      (node (ref "U5") (pin "4") (pinfunction "4_4") (pintype "passive"))
      (node (ref "U6") (pin "4") (pinfunction "4_4") (pintype "passive"))
      (node (ref "U7") (pin "4") (pinfunction "4_4") (pintype "passive"))
      (node (ref "U8") (pin "4") (pinfunction "4_4") (pintype "passive"))
      (node (ref "U9") (pin "4") (pinfunction "4_4") (pintype "passive"))
    )
    (net (code "49") (name "/XTAL1") (class "Default")
      (node (ref "C2") (pin "2") (pintype "passive"))
      (node (ref "R1") (pin "1") (pinfunction "1_1") (pintype "passive"))
      (node (ref "U0") (pin "34") (pinfunction "XTAL1_34") (pintype "passive"))
      (node (ref "Y1") (pin "1") (pinfunction "OSC1_1") (pintype "passive"))
    )
    (net (code "50") (name "/XTAL2") (class "Default")
      (node (ref "C1") (pin "2") (pintype "passive"))
      (node (ref "R1") (pin "2") (pinfunction "2_2") (pintype "passive"))
      (node (ref "U0") (pin "33") (pinfunction "XTAL2_33") (pintype "output"))
      (node (ref "Y1") (pin "2") (pinfunction "OSC2_2") (pintype "passive"))
    )
    (net (code "51") (name "AGND") (class "Default")
      (node (ref "C1") (pin "1") (pintype "passive"))
      (node (ref "C10") (pin "2") (pinfunction "2_2") (pintype "passive"))
      (node (ref "C11") (pin "1") (pinfunction "1_1") (pintype "passive"))
      (node (ref "C12") (pin "2") (pinfunction "2_2") (pintype "passive"))
      (node (ref "C18") (pin "2") (pinfunction "GND_2") (pintype "passive"))
      (node (ref "C19") (pin "2") (pinfunction "GND_2") (pintype "passive"))
      (node (ref "C2") (pin "1") (pintype "passive"))
      (node (ref "C3") (pin "1") (pintype "passive"))
      (node (ref "C4") (pin "1") (pintype "passive"))
      (node (ref "C5") (pin "1") (pintype "passive"))
      (node (ref "C6") (pin "1") (pintype "passive"))
      (node (ref "C7") (pin "1") (pintype "passive"))
      (node (ref "C8") (pin "1") (pintype "passive"))
      (node (ref "C9") (pin "1") (pinfunction "1_1") (pintype "passive"))
      (node (ref "D1") (pin "2") (pinfunction "K_2") (pintype "passive"))
      (node (ref "D11") (pin "2") (pinfunction "K_2") (pintype "passive"))
      (node (ref "D12") (pin "2") (pinfunction "K_2") (pintype "passive"))
      (node (ref "D13") (pin "2") (pinfunction "K_2") (pintype "passive"))
      (node (ref "D14") (pin "2") (pinfunction "K_2") (pintype "passive"))
      (node (ref "D15") (pin "2") (pinfunction "K_2") (pintype "passive"))
      (node (ref "D16") (pin "2") (pinfunction "K_2") (pintype "passive"))
      (node (ref "D17") (pin "2") (pinfunction "K_2") (pintype "passive"))
      (node (ref "D18") (pin "2") (pinfunction "K_2") (pintype "passive"))
      (node (ref "D2") (pin "2") (pinfunction "K_2") (pintype "passive"))
      (node (ref "D27") (pin "2") (pinfunction "2_2") (pintype "passive"))
      (node (ref "D3") (pin "2") (pinfunction "K_2") (pintype "passive"))
      (node (ref "D4") (pin "2") (pinfunction "K_2") (pintype "passive"))
      (node (ref "D5") (pin "2") (pinfunction "K_2") (pintype "passive"))
      (node (ref "D6") (pin "2") (pinfunction "K_2") (pintype "passive"))
      (node (ref "D7") (pin "2") (pinfunction "K_2") (pintype "passive"))
      (node (ref "D8") (pin "2") (pinfunction "K_2") (pintype "passive"))
      (node (ref "D9") (pin "1") (pinfunction "1_1") (pintype "passive"))
      (node (ref "P1") (pin "1") (pinfunction "1_1") (pintype "passive"))
      (node (ref "P1") (pin "11") (pinfunction "11_11") (pintype "passive"))
      (node (ref "P1") (pin "13") (pinfunction "13_13") (pintype "passive"))
      (node (ref "P1") (pin "15") (pinfunction "15_15") (pintype "passive"))
      (node (ref "P1") (pin "17") (pinfunction "17_17") (pintype "passive"))
      (node (ref "P1") (pin "19") (pinfunction "19_19") (pintype "passive"))
      (node (ref "P1") (pin "3") (pinfunction "3_3") (pintype "passive"))
      (node (ref "P1") (pin "5") (pinfunction "5_5") (pintype "passive"))
      (node (ref "P1") (pin "7") (pinfunction "7_7") (pintype "passive"))
      (node (ref "P1") (pin "9") (pinfunction "9_9") (pintype "passive"))
      (node (ref "P3") (pin "10") (pinfunction "10_10") (pintype "passive"))
      (node (ref "P3") (pin "12") (pinfunction "12_12") (pintype "passive"))
      (node (ref "P3") (pin "14") (pinfunction "14_14") (pintype "passive"))
      (node (ref "P3") (pin "16") (pinfunction "16_16") (pintype "passive"))
      (node (ref "P3") (pin "18") (pinfunction "18_18") (pintype "passive"))
      (node (ref "P3") (pin "2") (pinfunction "2_2") (pintype "passive"))
      (node (ref "P3") (pin "4") (pinfunction "4_4") (pintype "passive"))
      (node (ref "P3") (pin "6") (pinfunction "6_6") (pintype "passive"))
      (node (ref "P3") (pin "8") (pinfunction "8_8") (pintype "passive"))
      (node (ref "P5") (pin "6") (pinfunction "6_6") (pintype "passive"))
      (node (ref "P6") (pin "4") (pinfunction "4_4") (pintype "passive"))
      (node (ref "P9") (pin "4") (pinfunction "4_4") (pintype "passive"))
      (node (ref "Q0") (pin "2") (pinfunction "2_2") (pintype "passive"))
      (node (ref "Q1") (pin "2") (pinfunction "2_2") (pintype "passive"))
      (node (ref "Q2") (pin "2") (pinfunction "2_2") (pintype "passive"))
      (node (ref "Q3") (pin "2") (pinfunction "2_2") (pintype "passive"))
      (node (ref "Q4") (pin "2") (pinfunction "2_2") (pintype "passive"))
      (node (ref "Q5") (pin "2") (pinfunction "2_2") (pintype "passive"))
      (node (ref "Q6") (pin "2") (pinfunction "2_2") (pintype "passive"))
      (node (ref "Q7") (pin "2") (pinfunction "2_2") (pintype "passive"))
      (node (ref "R5") (pin "2") (pinfunction "2_2") (pintype "passive"))
      (node (ref "Rt") (pin "1") (pinfunction "1_1") (pintype "passive"))
      (node (ref "S1") (pin "1") (pinfunction "1_1") (pintype "passive"))
      (node (ref "U0") (pin "11") (pinfunction "GND_11") (pintype "power_in"))
      (node (ref "U0") (pin "32") (pinfunction "GND1_32") (pintype "power_in"))
      (node (ref "U0") (pin "62") (pinfunction "GND2_62") (pintype "power_in"))
      (node (ref "U0") (pin "81") (pinfunction "GND3_81") (pintype "power_in"))
      (node (ref "U0") (pin "99") (pinfunction "AGND_99") (pintype "power_in"))
      (node (ref "U1") (pin "2") (pinfunction "GND_2") (pintype "passive"))
      (node (ref "U3") (pin "1") (pinfunction "GND_1") (pintype "passive"))
      (node (ref "U4") (pin "3") (pinfunction "3_3") (pintype "passive"))
      (node (ref "U4") (pin "5") (pinfunction "5_5") (pintype "passive"))
    )
    (net (code "52") (name "Net-(C17-Pad1)") (class "Default")
      (node (ref "C17") (pin "1") (pinfunction "1_1") (pintype "passive"))
      (node (ref "R5") (pin "1") (pinfunction "1_1") (pintype "passive"))
      (node (ref "R6") (pin "2") (pinfunction "2_2") (pintype "passive"))
      (node (ref "U4") (pin "4") (pinfunction "4_4") (pintype "passive"))
    )
    (net (code "53") (name "Net-(D1-A)") (class "Default")
      (node (ref "D1") (pin "1") (pinfunction "A_1") (pintype "passive"))
      (node (ref "R38") (pin "1") (pinfunction "1_1") (pintype "passive"))
    )
    (net (code "54") (name "Net-(D2-A)") (class "Default")
      (node (ref "D2") (pin "1") (pinfunction "A_1") (pintype "passive"))
      (node (ref "R39") (pin "1") (pinfunction "1_1") (pintype "passive"))
    )
    (net (code "55") (name "Net-(D3-A)") (class "Default")
      (node (ref "D3") (pin "1") (pinfunction "A_1") (pintype "passive"))
      (node (ref "R40") (pin "1") (pinfunction "1_1") (pintype "passive"))
    )
    (net (code "56") (name "Net-(D4-A)") (class "Default")
      (node (ref "D4") (pin "1") (pinfunction "A_1") (pintype "passive"))
      (node (ref "R41") (pin "1") (pinfunction "1_1") (pintype "passive"))
    )
    (net (code "57") (name "Net-(D5-A)") (class "Default")
      (node (ref "D5") (pin "1") (pinfunction "A_1") (pintype "passive"))
      (node (ref "R42") (pin "1") (pinfunction "1_1") (pintype "passive"))
    )
    (net (code "58") (name "Net-(D6-A)") (class "Default")
      (node (ref "D6") (pin "1") (pinfunction "A_1") (pintype "passive"))
      (node (ref "R43") (pin "1") (pinfunction "1_1") (pintype "passive"))
    )
    (net (code "59") (name "Net-(D7-A)") (class "Default")
      (node (ref "D7") (pin "1") (pinfunction "A_1") (pintype "passive"))
      (node (ref "R44") (pin "1") (pinfunction "1_1") (pintype "passive"))
    )
    (net (code "60") (name "Net-(D8-A)") (class "Default")
      (node (ref "D8") (pin "1") (pinfunction "A_1") (pintype "passive"))
      (node (ref "R45") (pin "1") (pinfunction "1_1") (pintype "passive"))
    )
    (net (code "61") (name "Net-(D9-Pad2)") (class "Default")
      (node (ref "D9") (pin "2") (pinfunction "2_2") (pintype "passive"))
      (node (ref "L2") (pin "1") (pinfunction "1_1") (pintype "passive"))
      (node (ref "U4") (pin "2") (pinfunction "2_2") (pintype "passive"))
    )
    (net (code "62") (name "Net-(D11-A)") (class "Default")
      (node (ref "D11") (pin "1") (pinfunction "A_1") (pintype "passive"))
      (node (ref "R30") (pin "1") (pinfunction "1_1") (pintype "passive"))
    )
    (net (code "63") (name "Net-(D12-A)") (class "Default")
      (node (ref "D12") (pin "1") (pinfunction "A_1") (pintype "passive"))
      (node (ref "R31") (pin "1") (pinfunction "1_1") (pintype "passive"))
    )
    (net (code "64") (name "Net-(D13-A)") (class "Default")
      (node (ref "D13") (pin "1") (pinfunction "A_1") (pintype "passive"))
      (node (ref "R32") (pin "1") (pinfunction "1_1") (pintype "passive"))
    )
    (net (code "65") (name "Net-(D14-A)") (class "Default")
      (node (ref "D14") (pin "1") (pinfunction "A_1") (pintype "passive"))
      (node (ref "R33") (pin "1") (pinfunction "1_1") (pintype "passive"))
    )
    (net (code "66") (name "Net-(D15-A)") (class "Default")
      (node (ref "D15") (pin "1") (pinfunction "A_1") (pintype "passive"))
      (node (ref "R34") (pin "1") (pinfunction "1_1") (pintype "passive"))
    )
    (net (code "67") (name "Net-(D16-A)") (class "Default")
      (node (ref "D16") (pin "1") (pinfunction "A_1") (pintype "passive"))
      (node (ref "R35") (pin "1") (pinfunction "1_1") (pintype "passive"))
    )
    (net (code "68") (name "Net-(D17-A)") (class "Default")
      (node (ref "D17") (pin "1") (pinfunction "A_1") (pintype "passive"))
      (node (ref "R36") (pin "1") (pinfunction "1_1") (pintype "passive"))
    )
    (net (code "69") (name "Net-(D18-A)") (class "Default")
      (node (ref "D18") (pin "1") (pinfunction "A_1") (pintype "passive"))
      (node (ref "R37") (pin "1") (pinfunction "1_1") (pintype "passive"))
    )
    (net (code "70") (name "Net-(D27-Pad1)") (class "Default")
      (node (ref "D27") (pin "1") (pinfunction "1_1") (pintype "passive"))
      (node (ref "R46") (pin "2") (pinfunction "2_2") (pintype "passive"))
    )
    (net (code "71") (name "Net-(P1-Pad2)") (class "Default")
      (node (ref "P1") (pin "2") (pinfunction "2_2") (pintype "passive"))
      (node (ref "P2") (pin "1") (pinfunction "1_1") (pintype "passive"))
    )
    (net (code "72") (name "Net-(P1-Pad4)") (class "Default")
      (node (ref "P1") (pin "4") (pinfunction "4_4") (pintype "passive"))
      (node (ref "P2") (pin "3") (pinfunction "3_3") (pintype "passive"))
    )
    (net (code "73") (name "Net-(P1-Pad6)") (class "Default")
      (node (ref "P1") (pin "6") (pinfunction "6_6") (pintype "passive"))
      (node (ref "P2") (pin "5") (pinfunction "5_5") (pintype "passive"))
    )
    (net (code "74") (name "Net-(P1-Pad8)") (class "Default")
      (node (ref "P1") (pin "8") (pinfunction "8_8") (pintype "passive"))
      (node (ref "P2") (pin "7") (pinfunction "7_7") (pintype "passive"))
    )
    (net (code "75") (name "Net-(P1-Pad10)") (class "Default")
      (node (ref "P1") (pin "10") (pinfunction "10_10") (pintype "passive"))
      (node (ref "P2") (pin "9") (pinfunction "9_9") (pintype "passive"))
    )
    (net (code "76") (name "Net-(P1-Pad12)") (class "Default")
      (node (ref "P1") (pin "12") (pinfunction "12_12") (pintype "passive"))
      (node (ref "P2") (pin "11") (pinfunction "11_11") (pintype "passive"))
    )
    (net (code "77") (name "Net-(P1-Pad14)") (class "Default")
      (node (ref "P1") (pin "14") (pinfunction "14_14") (pintype "passive"))
      (node (ref "P2") (pin "13") (pinfunction "13_13") (pintype "passive"))
    )
    (net (code "78") (name "Net-(P1-Pad16)") (class "Default")
      (node (ref "P1") (pin "16") (pinfunction "16_16") (pintype "passive"))
      (node (ref "P2") (pin "15") (pinfunction "15_15") (pintype "passive"))
    )
    (net (code "79") (name "Net-(Q0-Pad1)") (class "Default")
      (node (ref "Q0") (pin "1") (pinfunction "1_1") (pintype "passive"))
      (node (ref "R17") (pin "2") (pinfunction "2_2") (pintype "passive"))
    )
    (net (code "80") (name "Net-(Q0-Pad3)") (class "Default")
      (node (ref "Q0") (pin "3") (pinfunction "3_3") (pintype "passive"))
      (node (ref "U5") (pin "2") (pinfunction "2_2") (pintype "passive"))
    )
    (net (code "81") (name "Net-(Q1-Pad1)") (class "Default")
      (node (ref "Q1") (pin "1") (pinfunction "1_1") (pintype "passive"))
      (node (ref "R18") (pin "2") (pinfunction "2_2") (pintype "passive"))
    )
    (net (code "82") (name "Net-(Q1-Pad3)") (class "Default")
      (node (ref "Q1") (pin "3") (pinfunction "3_3") (pintype "passive"))
      (node (ref "U6") (pin "2") (pinfunction "2_2") (pintype "passive"))
    )
    (net (code "83") (name "Net-(Q2-Pad1)") (class "Default")
      (node (ref "Q2") (pin "1") (pinfunction "1_1") (pintype "passive"))
      (node (ref "R19") (pin "2") (pinfunction "2_2") (pintype "passive"))
    )
    (net (code "84") (name "Net-(Q2-Pad3)") (class "Default")
      (node (ref "Q2") (pin "3") (pinfunction "3_3") (pintype "passive"))
      (node (ref "U7") (pin "2") (pinfunction "2_2") (pintype "passive"))
    )
    (net (code "85") (name "Net-(Q3-Pad1)") (class "Default")
      (node (ref "Q3") (pin "1") (pinfunction "1_1") (pintype "passive"))
      (node (ref "R20") (pin "2") (pinfunction "2_2") (pintype "passive"))
    )
    (net (code "86") (name "Net-(Q3-Pad3)") (class "Default")
      (node (ref "Q3") (pin "3") (pinfunction "3_3") (pintype "passive"))
      (node (ref "U8") (pin "2") (pinfunction "2_2") (pintype "passive"))
    )
    (net (code "87") (name "Net-(Q4-Pad1)") (class "Default")
      (node (ref "Q4") (pin "1") (pinfunction "1_1") (pintype "passive"))
      (node (ref "R21") (pin "2") (pinfunction "2_2") (pintype "passive"))
    )
    (net (code "88") (name "Net-(Q4-Pad3)") (class "Default")
      (node (ref "Q4") (pin "3") (pinfunction "3_3") (pintype "passive"))
      (node (ref "U9") (pin "2") (pinfunction "2_2") (pintype "passive"))
    )
    (net (code "89") (name "Net-(Q5-Pad1)") (class "Default")
      (node (ref "Q5") (pin "1") (pinfunction "1_1") (pintype "passive"))
      (node (ref "R22") (pin "2") (pinfunction "2_2") (pintype "passive"))
    )
    (net (code "90") (name "Net-(Q5-Pad3)") (class "Default")
      (node (ref "Q5") (pin "3") (pinfunction "3_3") (pintype "passive"))
      (node (ref "U10") (pin "2") (pinfunction "2_2") (pintype "passive"))
    )
    (net (code "91") (name "Net-(Q6-Pad1)") (class "Default")
      (node (ref "Q6") (pin "1") (pinfunction "1_1") (pintype "passive"))
      (node (ref "R23") (pin "2") (pinfunction "2_2") (pintype "passive"))
    )
    (net (code "92") (name "Net-(Q6-Pad3)") (class "Default")
      (node (ref "Q6") (pin "3") (pinfunction "3_3") (pintype "passive"))
      (node (ref "U11") (pin "2") (pinfunction "2_2") (pintype "passive"))
    )
    (net (code "93") (name "Net-(Q7-Pad1)") (class "Default")
      (node (ref "Q7") (pin "1") (pinfunction "1_1") (pintype "passive"))
      (node (ref "R24") (pin "2") (pinfunction "2_2") (pintype "passive"))
    )
    (net (code "94") (name "Net-(Q7-Pad3)") (class "Default")
      (node (ref "Q7") (pin "3") (pinfunction "3_3") (pintype "passive"))
      (node (ref "U12") (pin "2") (pinfunction "2_2") (pintype "passive"))
    )
    (net (code "95") (name "Net-(R9-Pad2)") (class "Default")
      (node (ref "R9") (pin "2") (pinfunction "2_2") (pintype "passive"))
      (node (ref "U5") (pin "1") (pinfunction "1_1") (pintype "passive"))
    )
    (net (code "96") (name "Net-(R10-Pad2)") (class "Default")
      (node (ref "R10") (pin "2") (pinfunction "2_2") (pintype "passive"))
      (node (ref "U6") (pin "1") (pinfunction "1_1") (pintype "passive"))
    )
    (net (code "97") (name "Net-(R11-Pad2)") (class "Default")
      (node (ref "R11") (pin "2") (pinfunction "2_2") (pintype "passive"))
      (node (ref "U7") (pin "1") (pinfunction "1_1") (pintype "passive"))
    )
    (net (code "98") (name "Net-(R12-Pad2)") (class "Default")
      (node (ref "R12") (pin "2") (pinfunction "2_2") (pintype "passive"))
      (node (ref "U8") (pin "1") (pinfunction "1_1") (pintype "passive"))
    )
    (net (code "99") (name "Net-(R13-Pad2)") (class "Default")
      (node (ref "R13") (pin "2") (pinfunction "2_2") (pintype "passive"))
      (node (ref "U9") (pin "1") (pinfunction "1_1") (pintype "passive"))
    )
    (net (code "100") (name "Net-(R14-Pad2)") (class "Default")
      (node (ref "R14") (pin "2") (pinfunction "2_2") (pintype "passive"))
      (node (ref "U10") (pin "1") (pinfunction "1_1") (pintype "passive"))
    )
    (net (code "101") (name "Net-(R15-Pad2)") (class "Default")
      (node (ref "R15") (pin "2") (pinfunction "2_2") (pintype "passive"))
      (node (ref "U11") (pin "1") (pinfunction "1_1") (pintype "passive"))
    )
    (net (code "102") (name "Net-(R16-Pad2)") (class "Default")
      (node (ref "R16") (pin "2") (pinfunction "2_2") (pintype "passive"))
      (node (ref "U12") (pin "1") (pinfunction "1_1") (pintype "passive"))
    )
    (net (code "103") (name "Net-(U0-AVCC)") (class "Default")
      (node (ref "C7") (pin "2") (pintype "passive"))
      (node (ref "L1") (pin "1") (pinfunction "1_1") (pintype "passive"))
      (node (ref "U0") (pin "100") (pinfunction "AVCC_100") (pintype "power_in"))
    )
    (net (code "104") (name "unconnected-(P1-Pad18)") (class "Default")
      (node (ref "P1") (pin "18") (pinfunction "18_18") (pintype "passive"))
    )
    (net (code "105") (name "unconnected-(P3-Pad17)") (class "Default")
      (node (ref "P3") (pin "17") (pinfunction "17_17") (pintype "passive"))
    )
    (net (code "106") (name "unconnected-(P3-Pad19)") (class "Default")
      (node (ref "P3") (pin "19") (pinfunction "19_19") (pintype "passive"))
    )
    (net (code "107") (name "unconnected-(P3-Pad20)") (class "Default")
      (node (ref "P3") (pin "20") (pinfunction "20_20") (pintype "passive"))
    )
    (net (code "108") (name "unconnected-(P6-Pad6)") (class "Default")
      (node (ref "P6") (pin "6") (pinfunction "6_6") (pintype "passive"))
    )
    (net (code "109") (name "unconnected-(P6-Pad8)") (class "Default")
      (node (ref "P6") (pin "8") (pinfunction "8_8") (pintype "passive"))
    )
    (net (code "110") (name "unconnected-(P6-Pad10)") (class "Default")
      (node (ref "P6") (pin "10") (pinfunction "10_10") (pintype "passive"))
    )
    (net (code "111") (name "unconnected-(P6-Pad12)") (class "Default")
      (node (ref "P6") (pin "12") (pinfunction "12_12") (pintype "passive"))
    )
    (net (code "112") (name "unconnected-(P6-Pad14)") (class "Default")
      (node (ref "P6") (pin "14") (pinfunction "14_14") (pintype "passive"))
    )
    (net (code "113") (name "unconnected-(P6-Pad16)") (class "Default")
      (node (ref "P6") (pin "16") (pinfunction "16_16") (pintype "passive"))
    )
    (net (code "114") (name "unconnected-(P6-Pad18)") (class "Default")
      (node (ref "P6") (pin "18") (pinfunction "18_18") (pintype "passive"))
    )
    (net (code "115") (name "unconnected-(P6-Pad20)") (class "Default")
      (node (ref "P6") (pin "20") (pinfunction "20_20") (pintype "passive"))
    )
    (net (code "116") (name "unconnected-(U0-(A8)PC0-Pad53)") (class "Default")
      (node (ref "U0") (pin "53") (pinfunction "(A8)PC0_53") (pintype "passive"))
    )
    (net (code "117") (name "unconnected-(U0-(A9)PC1-Pad54)") (class "Default")
      (node (ref "U0") (pin "54") (pinfunction "(A9)PC1_54") (pintype "passive"))
    )
    (net (code "118") (name "unconnected-(U0-(A10)PC2-Pad55)") (class "Default")
      (node (ref "U0") (pin "55") (pinfunction "(A10)PC2_55") (pintype "passive"))
    )
    (net (code "119") (name "unconnected-(U0-(A11)PC3-Pad56)") (class "Default")
      (node (ref "U0") (pin "56") (pinfunction "(A11)PC3_56") (pintype "passive"))
    )
    (net (code "120") (name "unconnected-(U0-(A12)PC4-Pad57)") (class "Default")
      (node (ref "U0") (pin "57") (pinfunction "(A12)PC4_57") (pintype "passive"))
    )
    (net (code "121") (name "unconnected-(U0-(A13)PC5-Pad58)") (class "Default")
      (node (ref "U0") (pin "58") (pinfunction "(A13)PC5_58") (pintype "passive"))
    )
    (net (code "122") (name "unconnected-(U0-(A14)PC6-Pad59)") (class "Default")
      (node (ref "U0") (pin "59") (pinfunction "(A14)PC6_59") (pintype "passive"))
    )
    (net (code "123") (name "unconnected-(U0-(A15)PC7-Pad60)") (class "Default")
      (node (ref "U0") (pin "60") (pinfunction "(A15)PC7_60") (pintype "passive"))
    )
    (net (code "124") (name "unconnected-(U0-(AD0)PA0-Pad78)") (class "Default")
      (node (ref "U0") (pin "78") (pinfunction "(AD0)PA0_78") (pintype "passive"))
    )
    (net (code "125") (name "unconnected-(U0-(AD1)PA1-Pad77)") (class "Default")
      (node (ref "U0") (pin "77") (pinfunction "(AD1)PA1_77") (pintype "passive"))
    )
    (net (code "126") (name "unconnected-(U0-(AD2)PA2-Pad76)") (class "Default")
      (node (ref "U0") (pin "76") (pinfunction "(AD2)PA2_76") (pintype "passive"))
    )
    (net (code "127") (name "unconnected-(U0-(AD3)PA3-Pad75)") (class "Default")
      (node (ref "U0") (pin "75") (pinfunction "(AD3)PA3_75") (pintype "passive"))
    )
    (net (code "128") (name "unconnected-(U0-(AD4)PA4-Pad74)") (class "Default")
      (node (ref "U0") (pin "74") (pinfunction "(AD4)PA4_74") (pintype "passive"))
    )
    (net (code "129") (name "unconnected-(U0-(AD5)PA5-Pad73)") (class "Default")
      (node (ref "U0") (pin "73") (pinfunction "(AD5)PA5_73") (pintype "passive"))
    )
    (net (code "130") (name "unconnected-(U0-(AD6)PA6-Pad72)") (class "Default")
      (node (ref "U0") (pin "72") (pinfunction "(AD6)PA6_72") (pintype "passive"))
    )
    (net (code "131") (name "unconnected-(U0-(AD7)PA7-Pad71)") (class "Default")
      (node (ref "U0") (pin "71") (pinfunction "(AD7)PA7_71") (pintype "passive"))
    )
    (net (code "132") (name "unconnected-(U0-(ALE)PG2-Pad70)") (class "Default")
      (node (ref "U0") (pin "70") (pinfunction "(ALE)PG2_70") (pintype "passive"))
    )
    (net (code "133") (name "unconnected-(U0-(CLKO{slash}ICP3{slash}INT7)PE7-Pad9)") (class "Default")
      (node (ref "U0") (pin "9") (pinfunction "(CLKO/ICP3/INT7)PE7_9") (pintype "passive"))
    )
    (net (code "134") (name "unconnected-(U0-(ICP1)PD4-Pad47)") (class "Default")
      (node (ref "U0") (pin "47") (pinfunction "(ICP1)PD4_47") (pintype "passive"))
    )
    (net (code "135") (name "unconnected-(U0-(OC0B)PG5-Pad1)") (class "Default")
      (node (ref "U0") (pin "1") (pinfunction "(OC0B)PG5_1") (pintype "passive"))
    )
    (net (code "136") (name "unconnected-(U0-(OC1A{slash}PCINT5)PB5-Pad24)") (class "Default")
      (node (ref "U0") (pin "24") (pinfunction "(OC1A/PCINT5)PB5_24") (pintype "passive"))
    )
    (net (code "137") (name "unconnected-(U0-(OC1B{slash}PCINT6)PB6-Pad25)") (class "Default")
      (node (ref "U0") (pin "25") (pinfunction "(OC1B/PCINT6)PB6_25") (pintype "passive"))
    )
    (net (code "138") (name "unconnected-(U0-(OC2A{slash}PCINT4)PB4-Pad23)") (class "Default")
      (node (ref "U0") (pin "23") (pinfunction "(OC2A/PCINT4)PB4_23") (pintype "passive"))
    )
    (net (code "139") (name "unconnected-(U0-(OC3A{slash}AIN1)PE3-Pad5)") (class "Default")
      (node (ref "U0") (pin "5") (pinfunction "(OC3A/AIN1)PE3_5") (pintype "passive"))
    )
    (net (code "140") (name "unconnected-(U0-(OC3B{slash}INT4)PE4-Pad6)") (class "Default")
      (node (ref "U0") (pin "6") (pinfunction "(OC3B/INT4)PE4_6") (pintype "passive"))
    )
    (net (code "141") (name "unconnected-(U0-(OC3C{slash}INT5)PE5-Pad7)") (class "Default")
      (node (ref "U0") (pin "7") (pinfunction "(OC3C/INT5)PE5_7") (pintype "passive"))
    )
    (net (code "142") (name "unconnected-(U0-(RD)PG1-Pad52)") (class "Default")
      (node (ref "U0") (pin "52") (pinfunction "(RD)PG1_52") (pintype "passive"))
    )
    (net (code "143") (name "unconnected-(U0-(RXD1{slash}INT2)PD2-Pad45)") (class "Default")
      (node (ref "U0") (pin "45") (pinfunction "(RXD1/INT2)PD2_45") (pintype "passive"))
    )
    (net (code "144") (name "unconnected-(U0-(SS{slash}PCINT0)PB0-Pad19)") (class "Default")
      (node (ref "U0") (pin "19") (pinfunction "(SS/PCINT0)PB0_19") (pintype "passive"))
    )
    (net (code "145") (name "unconnected-(U0-(T0)PD7-Pad50)") (class "Default")
      (node (ref "U0") (pin "50") (pinfunction "(T0)PD7_50") (pintype "passive"))
    )
    (net (code "146") (name "unconnected-(U0-(T1)PD6-Pad49)") (class "Default")
      (node (ref "U0") (pin "49") (pinfunction "(T1)PD6_49") (pintype "passive"))
    )
    (net (code "147") (name "unconnected-(U0-(T3{slash}INT6)PE6-Pad8)") (class "Default")
      (node (ref "U0") (pin "8") (pinfunction "(T3/INT6)PE6_8") (pintype "passive"))
    )
    (net (code "148") (name "unconnected-(U0-(TOSC1)PG4-Pad29)") (class "Default")
      (node (ref "U0") (pin "29") (pinfunction "(TOSC1)PG4_29") (pintype "passive"))
    )
    (net (code "149") (name "unconnected-(U0-(TOSC2)PG3-Pad28)") (class "Default")
      (node (ref "U0") (pin "28") (pinfunction "(TOSC2)PG3_28") (pintype "passive"))
    )
    (net (code "150") (name "unconnected-(U0-(TXD1{slash}INT3)PD3-Pad46)") (class "Default")
      (node (ref "U0") (pin "46") (pinfunction "(TXD1/INT3)PD3_46") (pintype "passive"))
    )
    (net (code "151") (name "unconnected-(U0-(WR)PG0-Pad51)") (class "Default")
      (node (ref "U0") (pin "51") (pinfunction "(WR)PG0_51") (pintype "passive"))
    )
    (net (code "152") (name "unconnected-(U0-(XCK0{slash}AIN0)PE2-Pad4)") (class "Default")
      (node (ref "U0") (pin "4") (pinfunction "(XCK0/AIN0)PE2_4") (pintype "passive"))
    )
    (net (code "153") (name "unconnected-(U0-(XCK1)PD5-Pad48)") (class "Default")
      (node (ref "U0") (pin "48") (pinfunction "(XCK1)PD5_48") (pintype "passive"))
    )
    (net (code "154") (name "unconnected-(U0-PH0(RXD2)-Pad12)") (class "Default")
      (node (ref "U0") (pin "12") (pinfunction "PH0(RXD2)_12") (pintype "passive"))
    )
    (net (code "155") (name "unconnected-(U0-PH1(TXD2)-Pad13)") (class "Default")
      (node (ref "U0") (pin "13") (pinfunction "PH1(TXD2)_13") (pintype "passive"))
    )
    (net (code "156") (name "unconnected-(U0-PH2(XCK2)-Pad14)") (class "Default")
      (node (ref "U0") (pin "14") (pinfunction "PH2(XCK2)_14") (pintype "passive"))
    )
    (net (code "157") (name "unconnected-(U0-PH3(OC4A)-Pad15)") (class "Default")
      (node (ref "U0") (pin "15") (pinfunction "PH3(OC4A)_15") (pintype "passive"))
    )
    (net (code "158") (name "unconnected-(U0-PH4(OC4B)-Pad16)") (class "Default")
      (node (ref "U0") (pin "16") (pinfunction "PH4(OC4B)_16") (pintype "passive"))
    )
    (net (code "159") (name "unconnected-(U0-PH5(OC4C)-Pad17)") (class "Default")
      (node (ref "U0") (pin "17") (pinfunction "PH5(OC4C)_17") (pintype "passive"))
    )
    (net (code "160") (name "unconnected-(U0-PH6(OC2B)-Pad18)") (class "Default")
      (node (ref "U0") (pin "18") (pinfunction "PH6(OC2B)_18") (pintype "passive"))
    )
    (net (code "161") (name "unconnected-(U0-PH7(T4)-Pad27)") (class "Default")
      (node (ref "U0") (pin "27") (pinfunction "PH7(T4)_27") (pintype "passive"))
    )
    (net (code "162") (name "unconnected-(U0-PJ0(RXD3{slash}PCINT9)-Pad63)") (class "Default")
      (node (ref "U0") (pin "63") (pinfunction "PJ0(RXD3/PCINT9)_63") (pintype "passive"))
    )
    (net (code "163") (name "unconnected-(U0-PJ1(TXD3{slash}PCINT10)-Pad64)") (class "Default")
      (node (ref "U0") (pin "64") (pinfunction "PJ1(TXD3/PCINT10)_64") (pintype "passive"))
    )
    (net (code "164") (name "unconnected-(U0-PJ2(XCK3{slash}PCINT11)-Pad65)") (class "Default")
      (node (ref "U0") (pin "65") (pinfunction "PJ2(XCK3/PCINT11)_65") (pintype "passive"))
    )
    (net (code "165") (name "unconnected-(U0-PJ3(PCINT12)-Pad66)") (class "Default")
      (node (ref "U0") (pin "66") (pinfunction "PJ3(PCINT12)_66") (pintype "passive"))
    )
    (net (code "166") (name "unconnected-(U0-PJ4(PCINT13)-Pad67)") (class "Default")
      (node (ref "U0") (pin "67") (pinfunction "PJ4(PCINT13)_67") (pintype "passive"))
    )
    (net (code "167") (name "unconnected-(U0-PJ5(PCINT14)-Pad68)") (class "Default")
      (node (ref "U0") (pin "68") (pinfunction "PJ5(PCINT14)_68") (pintype "passive"))
    )
    (net (code "168") (name "unconnected-(U0-PJ6(PCINT15)-Pad69)") (class "Default")
      (node (ref "U0") (pin "69") (pinfunction "PJ6(PCINT15)_69") (pintype "passive"))
    )
    (net (code "169") (name "unconnected-(U0-PJ7-Pad79)") (class "Default")
      (node (ref "U0") (pin "79") (pinfunction "PJ7_79") (pintype "passive"))
    )
    (net (code "170") (name "unconnected-(U0-PK0(ADC8{slash}PCINT16)-Pad89)") (class "Default")
      (node (ref "U0") (pin "89") (pinfunction "PK0(ADC8/PCINT16)_89") (pintype "passive"))
    )
    (net (code "171") (name "unconnected-(U0-PK1(ADC9{slash}PCINT17)-Pad88)") (class "Default")
      (node (ref "U0") (pin "88") (pinfunction "PK1(ADC9/PCINT17)_88") (pintype "passive"))
    )
    (net (code "172") (name "unconnected-(U0-PK2(ADC10{slash}PCINT18)-Pad87)") (class "Default")
      (node (ref "U0") (pin "87") (pinfunction "PK2(ADC10/PCINT18)_87") (pintype "passive"))
    )
    (net (code "173") (name "unconnected-(U0-PK3(ADC11{slash}PCINT19)-Pad86)") (class "Default")
      (node (ref "U0") (pin "86") (pinfunction "PK3(ADC11/PCINT19)_86") (pintype "passive"))
    )
    (net (code "174") (name "unconnected-(U0-PK4(ADC12{slash}PCINT20)-Pad85)") (class "Default")
      (node (ref "U0") (pin "85") (pinfunction "PK4(ADC12/PCINT20)_85") (pintype "passive"))
    )
    (net (code "175") (name "unconnected-(U0-PK5(ADC13{slash}PCINT21)-Pad84)") (class "Default")
      (node (ref "U0") (pin "84") (pinfunction "PK5(ADC13/PCINT21)_84") (pintype "passive"))
    )
    (net (code "176") (name "unconnected-(U0-PK6(ADC14{slash}PCINT22)-Pad83)") (class "Default")
      (node (ref "U0") (pin "83") (pinfunction "PK6(ADC14/PCINT22)_83") (pintype "passive"))
    )
    (net (code "177") (name "unconnected-(U0-PK7(ADC15{slash}PCINT23)-Pad82)") (class "Default")
      (node (ref "U0") (pin "82") (pinfunction "PK7(ADC15/PCINT23)_82") (pintype "passive"))
    )
  )
)
